# Simon_Tilts.net
KiCad netlist of a schematic drawn in EAGLE
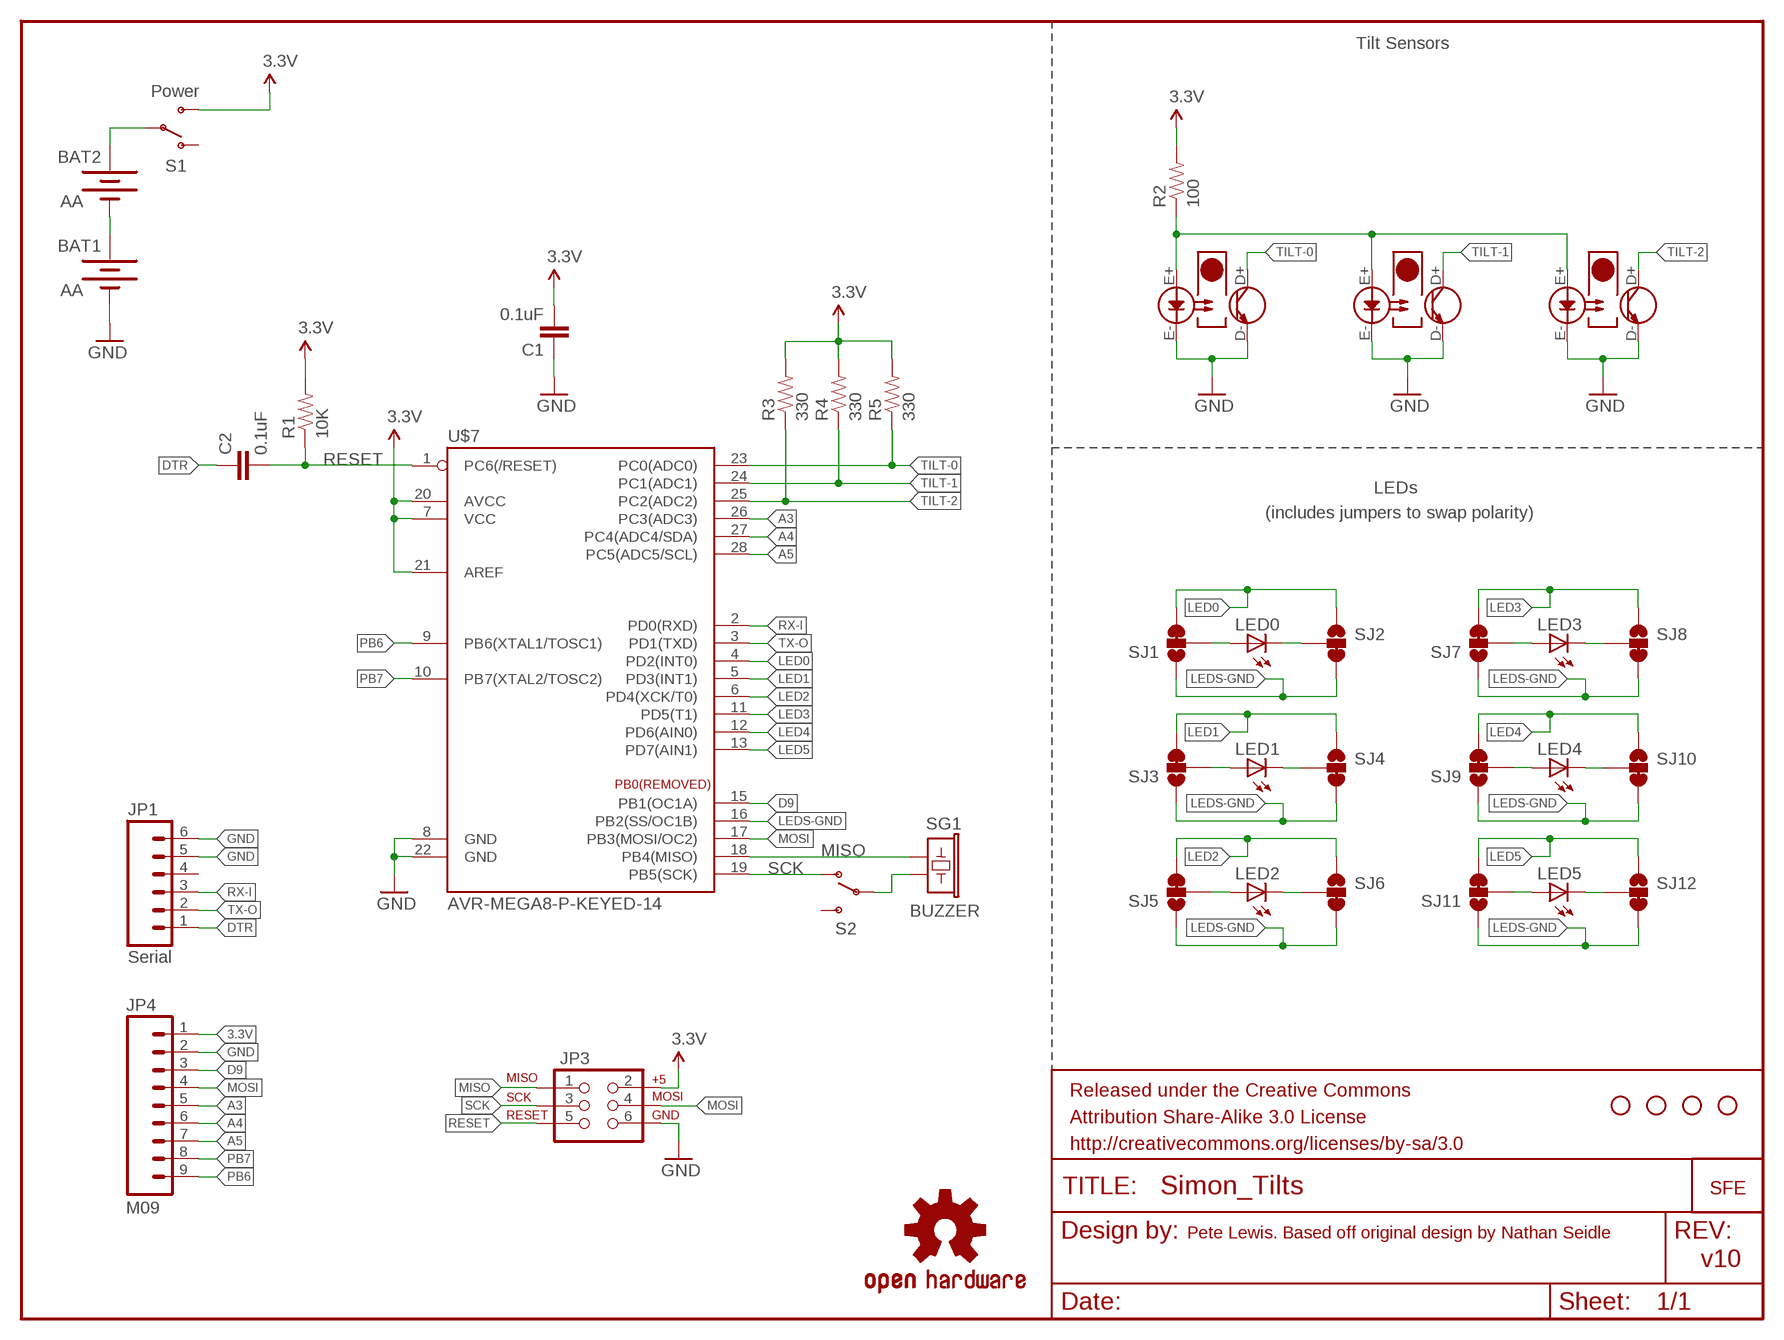
[diagram p0: schematic, sheet 1]

(export (version "E")
  (design (tool "Eeschema 10.0.6"))
  (components
    (comp (ref "BAT1")
      (value "AA")
      (footprint "eagle-import:BATTERY-AA-KIT")
      (libsource (lib "eagle-import") (part "BATTERYAA-KIT"))
    )
    (comp (ref "BAT2")
      (value "AA")
      (footprint "eagle-import:BATTERY-AA-KIT")
      (libsource (lib "eagle-import") (part "BATTERYAA-KIT"))
    )
    (comp (ref "C1")
      (value "0.1uF")
      (footprint "eagle-import:CAP-PTH-SMALL-KIT")
      (libsource (lib "eagle-import") (part "0.1UF-50V-20%(PTH)KIT-EZ"))
    )
    (comp (ref "C2")
      (value "0.1uF")
      (footprint "eagle-import:CAP-PTH-SMALL-KIT")
      (libsource (lib "eagle-import") (part "0.1UF-50V-20%(PTH)KIT-EZ"))
    )
    (comp (ref "FRAME1")
      (value "FRAME-LETTER")
      (footprint "eagle-import:CREATIVE_COMMONS")
      (libsource (lib "eagle-import") (part "FRAME-LETTER"))
    )
    (comp (ref "JP1")
      (value "Serial")
      (footprint "eagle-import:1X06-NOSILK")
      (libsource (lib "eagle-import") (part "M06-SFENOSILK"))
    )
    (comp (ref "JP2")
      (value "STAND-OFF")
      (footprint "eagle-import:STAND-OFF")
      (libsource (lib "eagle-import") (part "STAND-OFF"))
    )
    (comp (ref "JP3")
      (value "AVR_SPI_PRG_6NS")
      (footprint "eagle-import:2X3-NS")
      (libsource (lib "eagle-import") (part "AVR_SPI_PRG_6NS"))
    )
    (comp (ref "JP4")
      (value "M09")
      (footprint "eagle-import:1X09")
      (libsource (lib "eagle-import") (part "M09"))
    )
    (comp (ref "JP5")
      (value "STAND-OFF")
      (footprint "eagle-import:STAND-OFF")
      (libsource (lib "eagle-import") (part "STAND-OFF"))
    )
    (comp (ref "JP6")
      (value "STAND-OFF")
      (footprint "eagle-import:STAND-OFF")
      (libsource (lib "eagle-import") (part "STAND-OFF"))
    )
    (comp (ref "JP7")
      (value "STAND-OFF")
      (footprint "eagle-import:STAND-OFF")
      (libsource (lib "eagle-import") (part "STAND-OFF"))
    )
    (comp (ref "LED0")
      (value "LED5MM-KIT")
      (footprint "eagle-import:LED5MM-KIT")
      (libsource (lib "eagle-import") (part "LED5MM-KIT"))
    )
    (comp (ref "LED1")
      (value "LED5MM-KIT")
      (footprint "eagle-import:LED5MM-KIT")
      (libsource (lib "eagle-import") (part "LED5MM-KIT"))
    )
    (comp (ref "LED2")
      (value "LED5MM-KIT")
      (footprint "eagle-import:LED5MM-KIT")
      (libsource (lib "eagle-import") (part "LED5MM-KIT"))
    )
    (comp (ref "LED3")
      (value "LED5MM-KIT")
      (footprint "eagle-import:LED5MM-KIT")
      (libsource (lib "eagle-import") (part "LED5MM-KIT"))
    )
    (comp (ref "LED4")
      (value "LED5MM-KIT")
      (footprint "eagle-import:LED5MM-KIT")
      (libsource (lib "eagle-import") (part "LED5MM-KIT"))
    )
    (comp (ref "LED5")
      (value "LED5MM-KIT")
      (footprint "eagle-import:LED5MM-KIT")
      (libsource (lib "eagle-import") (part "LED5MM-KIT"))
    )
    (comp (ref "R1")
      (value "10K")
      (footprint "eagle-import:AXIAL-0.3-KIT")
      (libsource (lib "eagle-import") (part "10KOHM1/6W5%(PTH)KIT"))
    )
    (comp (ref "R2")
      (value "100")
      (footprint "eagle-import:AXIAL-0.3-KIT")
      (libsource (lib "eagle-import") (part "RESISTORAX-0.3-KIT"))
    )
    (comp (ref "R3")
      (value "330")
      (footprint "eagle-import:AXIAL-0.3-KIT")
      (libsource (lib "eagle-import") (part "RESISTORAX-0.3-KIT"))
    )
    (comp (ref "R4")
      (value "330")
      (footprint "eagle-import:AXIAL-0.3-KIT")
      (libsource (lib "eagle-import") (part "RESISTORAX-0.3-KIT"))
    )
    (comp (ref "R5")
      (value "330")
      (footprint "eagle-import:AXIAL-0.3-KIT")
      (libsource (lib "eagle-import") (part "RESISTORAX-0.3-KIT"))
    )
    (comp (ref "S1")
      (value "Power")
      (footprint "eagle-import:SWITCH-SPDT_KIT")
      (libsource (lib "eagle-import") (part "SWITCH-SPDTKIT"))
    )
    (comp (ref "S2")
      (value "SWITCH-SPDTKIT")
      (footprint "eagle-import:SWITCH-SPDT_KIT")
      (libsource (lib "eagle-import") (part "SWITCH-SPDTKIT"))
    )
    (comp (ref "SG1")
      (value "BUZZER")
      (footprint "eagle-import:BUZZER-12MM-KIT")
      (libsource (lib "eagle-import") (part "BUZZERPTH-KIT"))
    )
    (comp (ref "SJ1")
      (value "SOLDERJUMPER_2WAYS")
      (footprint "eagle-import:SJ_3")
      (libsource (lib "eagle-import") (part "SOLDERJUMPER_2WAYS"))
    )
    (comp (ref "SJ2")
      (value "SOLDERJUMPER_2WAYS")
      (footprint "eagle-import:SJ_3")
      (libsource (lib "eagle-import") (part "SOLDERJUMPER_2WAYS"))
    )
    (comp (ref "SJ3")
      (value "SOLDERJUMPER_2WAYS")
      (footprint "eagle-import:SJ_3")
      (libsource (lib "eagle-import") (part "SOLDERJUMPER_2WAYS"))
    )
    (comp (ref "SJ4")
      (value "SOLDERJUMPER_2WAYS")
      (footprint "eagle-import:SJ_3")
      (libsource (lib "eagle-import") (part "SOLDERJUMPER_2WAYS"))
    )
    (comp (ref "SJ5")
      (value "SOLDERJUMPER_2WAYS")
      (footprint "eagle-import:SJ_3")
      (libsource (lib "eagle-import") (part "SOLDERJUMPER_2WAYS"))
    )
    (comp (ref "SJ6")
      (value "SOLDERJUMPER_2WAYS")
      (footprint "eagle-import:SJ_3")
      (libsource (lib "eagle-import") (part "SOLDERJUMPER_2WAYS"))
    )
    (comp (ref "SJ7")
      (value "SOLDERJUMPER_2WAYS")
      (footprint "eagle-import:SJ_3")
      (libsource (lib "eagle-import") (part "SOLDERJUMPER_2WAYS"))
    )
    (comp (ref "SJ8")
      (value "SOLDERJUMPER_2WAYS")
      (footprint "eagle-import:SJ_3")
      (libsource (lib "eagle-import") (part "SOLDERJUMPER_2WAYS"))
    )
    (comp (ref "SJ9")
      (value "SOLDERJUMPER_2WAYS")
      (footprint "eagle-import:SJ_3")
      (libsource (lib "eagle-import") (part "SOLDERJUMPER_2WAYS"))
    )
    (comp (ref "SJ10")
      (value "SOLDERJUMPER_2WAYS")
      (footprint "eagle-import:SJ_3")
      (libsource (lib "eagle-import") (part "SOLDERJUMPER_2WAYS"))
    )
    (comp (ref "SJ11")
      (value "SOLDERJUMPER_2WAYS")
      (footprint "eagle-import:SJ_3")
      (libsource (lib "eagle-import") (part "SOLDERJUMPER_2WAYS"))
    )
    (comp (ref "SJ12")
      (value "SOLDERJUMPER_2WAYS")
      (footprint "eagle-import:SJ_3")
      (libsource (lib "eagle-import") (part "SOLDERJUMPER_2WAYS"))
    )
    (comp (ref "U$1")
      (value "LOGO-SFENEW")
      (footprint "eagle-import:SFE-NEW-WEBLOGO")
      (libsource (lib "eagle-import") (part "LOGO-SFENEW"))
    )
    (comp (ref "U$3")
      (value "OSHW-LOGOS")
      (footprint "eagle-import:OSHW-LOGO-S")
      (libsource (lib "eagle-import") (part "OSHW-LOGOS"))
    )
    (comp (ref "U$4")
      (value "TILT_SENSORV5")
      (footprint "eagle-import:TILT_SENSOR_V5")
      (libsource (lib "eagle-import") (part "TILT_SENSORV5"))
    )
    (comp (ref "U$5")
      (value "TILT_SENSORV5")
      (footprint "eagle-import:TILT_SENSOR_V5")
      (libsource (lib "eagle-import") (part "TILT_SENSORV5"))
    )
    (comp (ref "U$6")
      (value "TILT_SENSORV5")
      (footprint "eagle-import:TILT_SENSOR_V5")
      (libsource (lib "eagle-import") (part "TILT_SENSORV5"))
    )
    (comp (ref "U$7")
      (value "AVR-MEGA8-P-KEYED-14")
      (footprint "eagle-import:DIL28-3_KEYED-14")
      (libsource (lib "eagle-import") (part "AVR-MEGA8-P-KEYED-14"))
    )
  )
  (nets
    (net (code "1") (name "3.3V") (class "Default")
      (node (ref "C1") (pin "2") (pinfunction "2_2") (pintype "passive"))
      (node (ref "JP3") (pin "2") (pinfunction "2_2") (pintype "passive"))
      (node (ref "JP4") (pin "1") (pinfunction "1_1") (pintype "passive"))
      (node (ref "R1") (pin "P$2") (pinfunction "2_P$2") (pintype "passive"))
      (node (ref "R2") (pin "P$2") (pinfunction "2_P$2") (pintype "passive"))
      (node (ref "R3") (pin "P$2") (pinfunction "2_P$2") (pintype "passive"))
      (node (ref "R4") (pin "P$2") (pinfunction "2_P$2") (pintype "passive"))
      (node (ref "R5") (pin "P$2") (pinfunction "2_P$2") (pintype "passive"))
      (node (ref "S1") (pin "3") (pinfunction "S_3") (pintype "passive"))
      (node (ref "U$7") (pin "20") (pinfunction "AVCC_20") (pintype "bidirectional"))
      (node (ref "U$7") (pin "21") (pinfunction "AREF_21") (pintype "bidirectional"))
      (node (ref "U$7") (pin "7") (pinfunction "VCC_7") (pintype "bidirectional"))
    )
    (net (code "2") (name "A3") (class "Default")
      (node (ref "JP4") (pin "5") (pinfunction "5_5") (pintype "passive"))
      (node (ref "U$7") (pin "26") (pinfunction "PC3(ADC3)_26") (pintype "bidirectional"))
    )
    (net (code "3") (name "A4") (class "Default")
      (node (ref "JP4") (pin "6") (pinfunction "6_6") (pintype "passive"))
      (node (ref "U$7") (pin "27") (pinfunction "PC4(ADC4/SDA)_27") (pintype "bidirectional"))
    )
    (net (code "4") (name "A5") (class "Default")
      (node (ref "JP4") (pin "7") (pinfunction "7_7") (pintype "passive"))
      (node (ref "U$7") (pin "28") (pinfunction "PC5(ADC5/SCL)_28") (pintype "bidirectional"))
    )
    (net (code "5") (name "D9") (class "Default")
      (node (ref "JP4") (pin "3") (pinfunction "3_3") (pintype "passive"))
      (node (ref "U$7") (pin "15") (pinfunction "PB1(OC1A)_15") (pintype "bidirectional"))
    )
    (net (code "6") (name "DTR") (class "Default")
      (node (ref "C2") (pin "1") (pinfunction "1_1") (pintype "passive"))
      (node (ref "JP1") (pin "1") (pinfunction "1_1") (pintype "passive"))
    )
    (net (code "7") (name "GND") (class "Default")
      (node (ref "BAT1") (pin "GND@1") (pinfunction "-_GND@1") (pintype "power_in"))
      (node (ref "C1") (pin "1") (pinfunction "1_1") (pintype "passive"))
      (node (ref "JP1") (pin "5") (pinfunction "5_5") (pintype "passive"))
      (node (ref "JP1") (pin "6") (pinfunction "6_6") (pintype "passive"))
      (node (ref "JP3") (pin "6") (pinfunction "6_6") (pintype "passive"))
      (node (ref "JP4") (pin "2") (pinfunction "2_2") (pintype "passive"))
      (node (ref "U$4") (pin "D-") (pinfunction "D-_D-") (pintype "bidirectional"))
      (node (ref "U$4") (pin "E-") (pinfunction "E-_E-") (pintype "bidirectional"))
      (node (ref "U$5") (pin "D-") (pinfunction "D-_D-") (pintype "bidirectional"))
      (node (ref "U$5") (pin "E-") (pinfunction "E-_E-") (pintype "bidirectional"))
      (node (ref "U$6") (pin "D-") (pinfunction "D-_D-") (pintype "bidirectional"))
      (node (ref "U$6") (pin "E-") (pinfunction "E-_E-") (pintype "bidirectional"))
      (node (ref "U$7") (pin "22") (pinfunction "GND_22") (pintype "bidirectional"))
      (node (ref "U$7") (pin "8") (pinfunction "GND_8") (pintype "bidirectional"))
    )
    (net (code "8") (name "LED0") (class "Default")
      (node (ref "SJ1") (pin "3") (pinfunction "3_3") (pintype "passive"))
      (node (ref "SJ2") (pin "1") (pinfunction "1_1") (pintype "passive"))
      (node (ref "U$7") (pin "4") (pinfunction "PD2(INT0)_4") (pintype "bidirectional"))
    )
    (net (code "9") (name "LED1") (class "Default")
      (node (ref "SJ3") (pin "3") (pinfunction "3_3") (pintype "passive"))
      (node (ref "SJ4") (pin "1") (pinfunction "1_1") (pintype "passive"))
      (node (ref "U$7") (pin "5") (pinfunction "PD3(INT1)_5") (pintype "bidirectional"))
    )
    (net (code "10") (name "LED2") (class "Default")
      (node (ref "SJ5") (pin "3") (pinfunction "3_3") (pintype "passive"))
      (node (ref "SJ6") (pin "1") (pinfunction "1_1") (pintype "passive"))
      (node (ref "U$7") (pin "6") (pinfunction "PD4(XCK/T0)_6") (pintype "bidirectional"))
    )
    (net (code "11") (name "LED3") (class "Default")
      (node (ref "SJ7") (pin "3") (pinfunction "3_3") (pintype "passive"))
      (node (ref "SJ8") (pin "1") (pinfunction "1_1") (pintype "passive"))
      (node (ref "U$7") (pin "11") (pinfunction "PD5(T1)_11") (pintype "bidirectional"))
    )
    (net (code "12") (name "LED4") (class "Default")
      (node (ref "SJ10") (pin "1") (pinfunction "1_1") (pintype "passive"))
      (node (ref "SJ9") (pin "3") (pinfunction "3_3") (pintype "passive"))
      (node (ref "U$7") (pin "12") (pinfunction "PD6(AIN0)_12") (pintype "bidirectional"))
    )
    (net (code "13") (name "LED5") (class "Default")
      (node (ref "SJ11") (pin "3") (pinfunction "3_3") (pintype "passive"))
      (node (ref "SJ12") (pin "1") (pinfunction "1_1") (pintype "passive"))
      (node (ref "U$7") (pin "13") (pinfunction "PD7(AIN1)_13") (pintype "bidirectional"))
    )
    (net (code "14") (name "LEDS-GND") (class "Default")
      (node (ref "SJ1") (pin "1") (pinfunction "1_1") (pintype "passive"))
      (node (ref "SJ10") (pin "3") (pinfunction "3_3") (pintype "passive"))
      (node (ref "SJ11") (pin "1") (pinfunction "1_1") (pintype "passive"))
      (node (ref "SJ12") (pin "3") (pinfunction "3_3") (pintype "passive"))
      (node (ref "SJ2") (pin "3") (pinfunction "3_3") (pintype "passive"))
      (node (ref "SJ3") (pin "1") (pinfunction "1_1") (pintype "passive"))
      (node (ref "SJ4") (pin "3") (pinfunction "3_3") (pintype "passive"))
      (node (ref "SJ5") (pin "1") (pinfunction "1_1") (pintype "passive"))
      (node (ref "SJ6") (pin "3") (pinfunction "3_3") (pintype "passive"))
      (node (ref "SJ7") (pin "1") (pinfunction "1_1") (pintype "passive"))
      (node (ref "SJ8") (pin "3") (pinfunction "3_3") (pintype "passive"))
      (node (ref "SJ9") (pin "1") (pinfunction "1_1") (pintype "passive"))
      (node (ref "U$7") (pin "16") (pinfunction "PB2(SS/OC1B)_16") (pintype "bidirectional"))
    )
    (net (code "15") (name "MISO") (class "Default")
      (node (ref "JP3") (pin "1") (pinfunction "1_1") (pintype "passive"))
      (node (ref "SG1") (pin "+") (pinfunction "1_+") (pintype "passive"))
      (node (ref "U$7") (pin "18") (pinfunction "PB4(MISO)_18") (pintype "bidirectional"))
    )
    (net (code "16") (name "MOSI") (class "Default")
      (node (ref "JP3") (pin "4") (pinfunction "4_4") (pintype "passive"))
      (node (ref "JP4") (pin "4") (pinfunction "4_4") (pintype "passive"))
      (node (ref "U$7") (pin "17") (pinfunction "PB3(MOSI/OC2)_17") (pintype "bidirectional"))
    )
    (net (code "17") (name "Net-(BAT1-+)") (class "Default")
      (node (ref "BAT1") (pin "PWR@1") (pinfunction "+_PWR@1") (pintype "power_in"))
      (node (ref "BAT2") (pin "GND@1") (pinfunction "-_GND@1") (pintype "power_in"))
    )
    (net (code "18") (name "Net-(BAT2-+)") (class "Default")
      (node (ref "BAT2") (pin "PWR@1") (pinfunction "+_PWR@1") (pintype "power_in"))
      (node (ref "S1") (pin "2") (pinfunction "P_2") (pintype "passive"))
    )
    (net (code "19") (name "Net-(LED0-C)") (class "Default")
      (node (ref "LED0") (pin "K") (pinfunction "C_K") (pintype "passive"))
      (node (ref "SJ2") (pin "2") (pinfunction "2_2") (pintype "passive"))
    )
    (net (code "20") (name "Net-(LED0-PadA)") (class "Default")
      (node (ref "LED0") (pin "A") (pinfunction "A_A") (pintype "passive"))
      (node (ref "SJ1") (pin "2") (pinfunction "2_2") (pintype "passive"))
    )
    (net (code "21") (name "Net-(LED1-C)") (class "Default")
      (node (ref "LED1") (pin "K") (pinfunction "C_K") (pintype "passive"))
      (node (ref "SJ4") (pin "2") (pinfunction "2_2") (pintype "passive"))
    )
    (net (code "22") (name "Net-(LED1-PadA)") (class "Default")
      (node (ref "LED1") (pin "A") (pinfunction "A_A") (pintype "passive"))
      (node (ref "SJ3") (pin "2") (pinfunction "2_2") (pintype "passive"))
    )
    (net (code "23") (name "Net-(LED2-C)") (class "Default")
      (node (ref "LED2") (pin "K") (pinfunction "C_K") (pintype "passive"))
      (node (ref "SJ6") (pin "2") (pinfunction "2_2") (pintype "passive"))
    )
    (net (code "24") (name "Net-(LED2-PadA)") (class "Default")
      (node (ref "LED2") (pin "A") (pinfunction "A_A") (pintype "passive"))
      (node (ref "SJ5") (pin "2") (pinfunction "2_2") (pintype "passive"))
    )
    (net (code "25") (name "Net-(LED3-C)") (class "Default")
      (node (ref "LED3") (pin "K") (pinfunction "C_K") (pintype "passive"))
      (node (ref "SJ8") (pin "2") (pinfunction "2_2") (pintype "passive"))
    )
    (net (code "26") (name "Net-(LED3-PadA)") (class "Default")
      (node (ref "LED3") (pin "A") (pinfunction "A_A") (pintype "passive"))
      (node (ref "SJ7") (pin "2") (pinfunction "2_2") (pintype "passive"))
    )
    (net (code "27") (name "Net-(LED4-C)") (class "Default")
      (node (ref "LED4") (pin "K") (pinfunction "C_K") (pintype "passive"))
      (node (ref "SJ10") (pin "2") (pinfunction "2_2") (pintype "passive"))
    )
    (net (code "28") (name "Net-(LED4-PadA)") (class "Default")
      (node (ref "LED4") (pin "A") (pinfunction "A_A") (pintype "passive"))
      (node (ref "SJ9") (pin "2") (pinfunction "2_2") (pintype "passive"))
    )
    (net (code "29") (name "Net-(LED5-C)") (class "Default")
      (node (ref "LED5") (pin "K") (pinfunction "C_K") (pintype "passive"))
      (node (ref "SJ12") (pin "2") (pinfunction "2_2") (pintype "passive"))
    )
    (net (code "30") (name "Net-(LED5-PadA)") (class "Default")
      (node (ref "LED5") (pin "A") (pinfunction "A_A") (pintype "passive"))
      (node (ref "SJ11") (pin "2") (pinfunction "2_2") (pintype "passive"))
    )
    (net (code "31") (name "Net-(R2-1)") (class "Default")
      (node (ref "R2") (pin "P$1") (pinfunction "1_P$1") (pintype "passive"))
      (node (ref "U$4") (pin "E+") (pinfunction "E+_E+") (pintype "bidirectional"))
      (node (ref "U$5") (pin "E+") (pinfunction "E+_E+") (pintype "bidirectional"))
      (node (ref "U$6") (pin "E+") (pinfunction "E+_E+") (pintype "bidirectional"))
    )
    (net (code "32") (name "Net-(S2-P)") (class "Default")
      (node (ref "S2") (pin "2") (pinfunction "P_2") (pintype "passive"))
      (node (ref "SG1") (pin "-") (pinfunction "2_-") (pintype "passive"))
    )
    (net (code "33") (name "PB6") (class "Default")
      (node (ref "JP4") (pin "9") (pinfunction "9_9") (pintype "passive"))
      (node (ref "U$7") (pin "9") (pinfunction "PB6(XTAL1/TOSC1)_9") (pintype "bidirectional"))
    )
    (net (code "34") (name "PB7") (class "Default")
      (node (ref "JP4") (pin "8") (pinfunction "8_8") (pintype "passive"))
      (node (ref "U$7") (pin "10") (pinfunction "PB7(XTAL2/TOSC2)_10") (pintype "bidirectional"))
    )
    (net (code "35") (name "RESET") (class "Default")
      (node (ref "C2") (pin "2") (pinfunction "2_2") (pintype "passive"))
      (node (ref "JP3") (pin "5") (pinfunction "5_5") (pintype "passive"))
      (node (ref "R1") (pin "P$1") (pinfunction "1_P$1") (pintype "passive"))
      (node (ref "U$7") (pin "1") (pinfunction "PC6(/RESET)_1") (pintype "bidirectional"))
    )
    (net (code "36") (name "RX-I") (class "Default")
      (node (ref "JP1") (pin "3") (pinfunction "3_3") (pintype "passive"))
      (node (ref "U$7") (pin "2") (pinfunction "PD0(RXD)_2") (pintype "bidirectional"))
    )
    (net (code "37") (name "SCK") (class "Default")
      (node (ref "JP3") (pin "3") (pinfunction "3_3") (pintype "passive"))
      (node (ref "S2") (pin "1") (pinfunction "O_1") (pintype "passive"))
      (node (ref "U$7") (pin "19") (pinfunction "PB5(SCK)_19") (pintype "bidirectional"))
    )
    (net (code "38") (name "TILT-0") (class "Default")
      (node (ref "R5") (pin "P$1") (pinfunction "1_P$1") (pintype "passive"))
      (node (ref "U$4") (pin "D+") (pinfunction "D+_D+") (pintype "bidirectional"))
      (node (ref "U$7") (pin "23") (pinfunction "PC0(ADC0)_23") (pintype "bidirectional"))
    )
    (net (code "39") (name "TILT-1") (class "Default")
      (node (ref "R4") (pin "P$1") (pinfunction "1_P$1") (pintype "passive"))
      (node (ref "U$5") (pin "D+") (pinfunction "D+_D+") (pintype "bidirectional"))
      (node (ref "U$7") (pin "24") (pinfunction "PC1(ADC1)_24") (pintype "bidirectional"))
    )
    (net (code "40") (name "TILT-2") (class "Default")
      (node (ref "R3") (pin "P$1") (pinfunction "1_P$1") (pintype "passive"))
      (node (ref "U$6") (pin "D+") (pinfunction "D+_D+") (pintype "bidirectional"))
      (node (ref "U$7") (pin "25") (pinfunction "PC2(ADC2)_25") (pintype "bidirectional"))
    )
    (net (code "41") (name "TX-O") (class "Default")
      (node (ref "JP1") (pin "2") (pinfunction "2_2") (pintype "passive"))
      (node (ref "U$7") (pin "3") (pinfunction "PD1(TXD)_3") (pintype "bidirectional"))
    )
    (net (code "42") (name "unconnected-(JP1-Pad4)") (class "Default")
      (node (ref "JP1") (pin "4") (pinfunction "4_4") (pintype "passive"))
    )
    (net (code "43") (name "unconnected-(S1-O-Pad1)") (class "Default")
      (node (ref "S1") (pin "1") (pinfunction "O_1") (pintype "passive"))
    )
    (net (code "44") (name "unconnected-(S2-S-Pad3)") (class "Default")
      (node (ref "S2") (pin "3") (pinfunction "S_3") (pintype "passive"))
    )
  )
)
